# SimpleFPGA_SI_Demo.net
KiCad netlist of a schematic drawn in Altium Designer
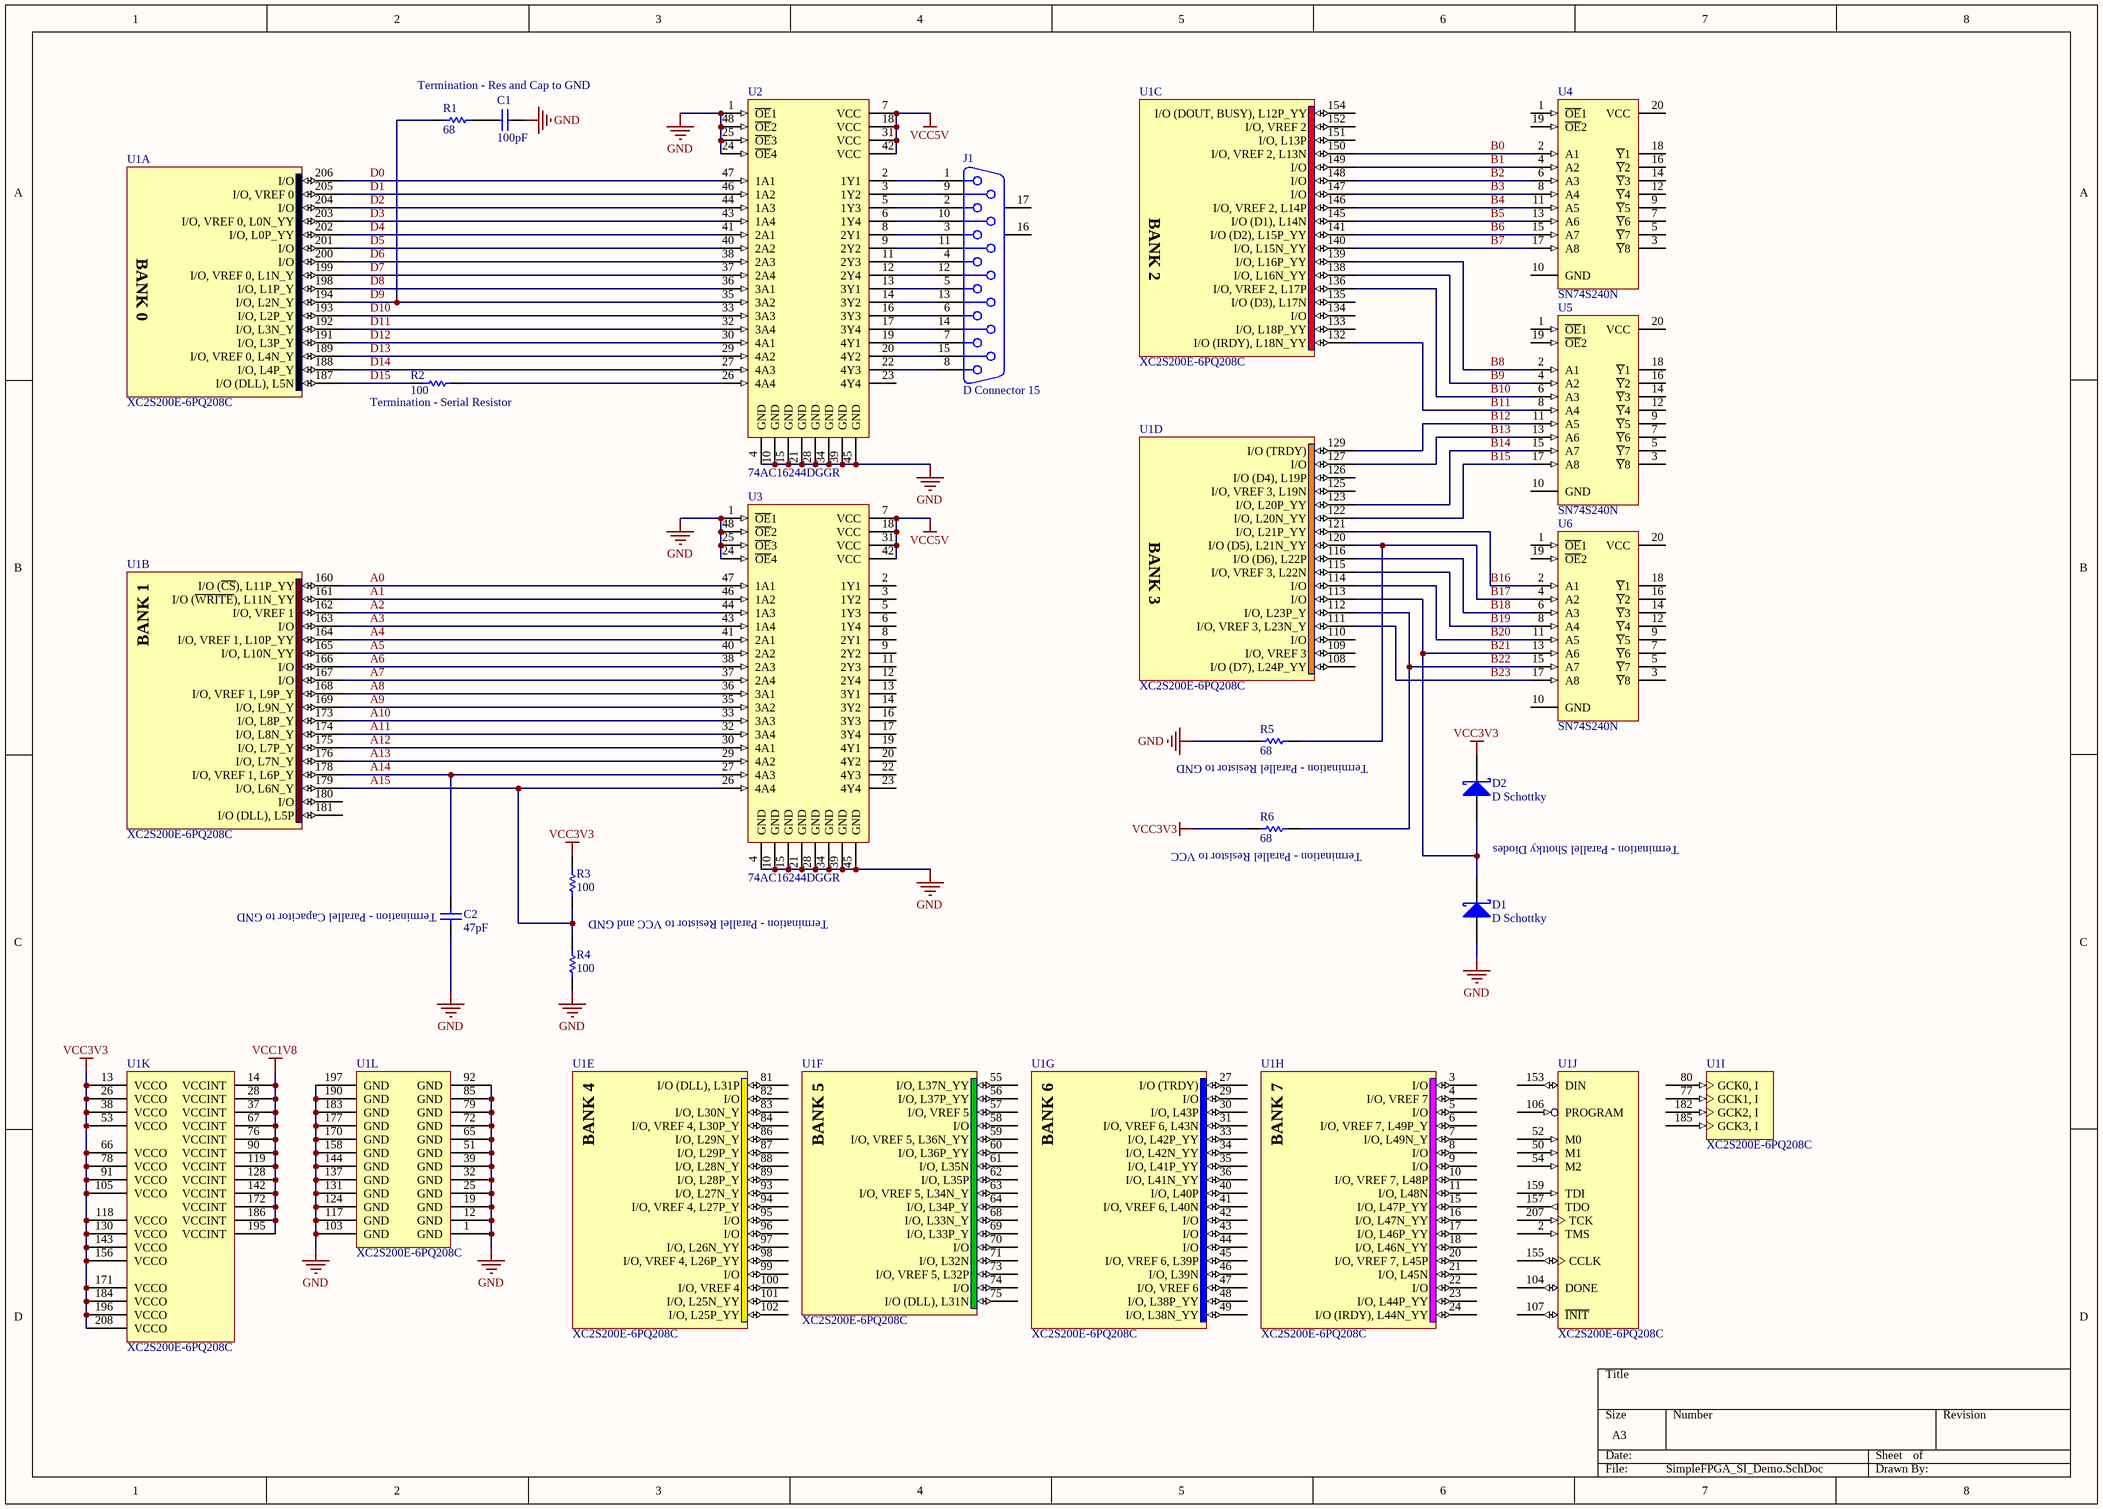
[diagram p0: SimpleFPGA_SI_Demo.SchDoc]

(export (version "E")
  (design (tool "Eeschema 10.0.6"))
  (components
    (comp (ref "C1")
      (value "100pF")
      (footprint "RAD-0.3")
      (description "Capacitor")
      (fields (field (name "Comment") "Cap"))
      (libsource (lib "Miscellaneous Devices") (part "Cap"))
    )
    (comp (ref "C2")
      (value "47pF")
      (footprint "RAD-0.3")
      (description "Capacitor")
      (fields (field (name "Comment") "Cap"))
      (libsource (lib "Miscellaneous Devices") (part "Cap"))
    )
    (comp (ref "D1")
      (value "D Schottky")
      (footprint "SMB")
      (description "Schottky Diode")
      (libsource (lib "Miscellaneous Devices") (part "D Schottky"))
    )
    (comp (ref "D2")
      (value "D Schottky")
      (footprint "SMB")
      (description "Schottky Diode")
      (libsource (lib "Miscellaneous Devices") (part "D Schottky"))
    )
    (comp (ref "J1")
      (value "D Connector 15")
      (footprint "DSUB1.385-2H15")
      (description "Receptacle Assembly, 15 Position, Right Angle")
      (libsource (lib "Miscellaneous Connectors") (part "D Connector 15"))
    )
    (comp (ref "R1")
      (value "68")
      (footprint "AXIAL-0.3")
      (description "Resistor")
      (fields (field (name "Comment") "Res1"))
      (libsource (lib "Miscellaneous Devices") (part "Res1"))
    )
    (comp (ref "R2")
      (value "100")
      (footprint "AXIAL-0.3")
      (description "Resistor")
      (fields (field (name "Comment") "Res1"))
      (libsource (lib "Miscellaneous Devices") (part "Res1"))
    )
    (comp (ref "R3")
      (value "100")
      (footprint "AXIAL-0.3")
      (description "Resistor")
      (fields (field (name "Comment") "Res1"))
      (libsource (lib "Miscellaneous Devices") (part "Res1"))
    )
    (comp (ref "R4")
      (value "100")
      (footprint "AXIAL-0.3")
      (description "Resistor")
      (fields (field (name "Comment") "Res1"))
      (libsource (lib "Miscellaneous Devices") (part "Res1"))
    )
    (comp (ref "R5")
      (value "68")
      (footprint "AXIAL-0.3")
      (description "Resistor")
      (fields (field (name "Comment") "Res1"))
      (libsource (lib "Miscellaneous Devices") (part "Res1"))
    )
    (comp (ref "R6")
      (value "68")
      (footprint "AXIAL-0.3")
      (description "Resistor")
      (fields (field (name "Comment") "Res1"))
      (libsource (lib "Miscellaneous Devices") (part "Res1"))
    )
    (comp (ref "U1")
      (value "XC2S200E-6PQ208C")
      (footprint "PQ208_N")
      (description "Spartan-IIE 1.8V FPGA, 208-Pin PQFP, Standard Performance, Commercial Grade")
      (libsource (lib "Xilinx Spartan-IIE") (part "XC2S200E-6PQ208C"))
    )
    (comp (ref "U2")
      (value "74AC16244DGGR")
      (footprint "DGG048")
      (description "16-Bit Buffer/Line Driver with 3-State Outputs")
      (libsource (lib "TI Logic Buffer Line Driver") (part "74AC16244DGGR"))
    )
    (comp (ref "U3")
      (value "74AC16244DGGR")
      (footprint "DGG048")
      (description "16-Bit Buffer/Line Driver with 3-State Outputs")
      (libsource (lib "TI Logic Buffer Line Driver") (part "74AC16244DGGR"))
    )
    (comp (ref "U4")
      (value "SN74S240N")
      (footprint "N020")
      (description "Octal Buffer and Line Driver with 3-State Outputs")
      (libsource (lib "TI Logic Buffer Line Driver") (part "SN74S240N"))
    )
    (comp (ref "U5")
      (value "SN74S240N")
      (footprint "N020")
      (description "Octal Buffer and Line Driver with 3-State Outputs")
      (libsource (lib "TI Logic Buffer Line Driver") (part "SN74S240N"))
    )
    (comp (ref "U6")
      (value "SN74S240N")
      (footprint "N020")
      (description "Octal Buffer and Line Driver with 3-State Outputs")
      (libsource (lib "TI Logic Buffer Line Driver") (part "SN74S240N"))
    )
  )
  (nets
    (net (code "1") (name "/A0") (class "Default")
      (node (ref "U1") (pin "160") (pinfunction "I/O_(~{CS}),_L11P_YY_160") (pintype "bidirectional"))
      (node (ref "U3") (pin "47") (pinfunction "1A1_47") (pintype "input"))
    )
    (net (code "2") (name "/A1") (class "Default")
      (node (ref "U1") (pin "161") (pinfunction "I/O_(~{WRITE}),_L11N_YY_161") (pintype "bidirectional"))
      (node (ref "U3") (pin "46") (pinfunction "1A2_46") (pintype "input"))
    )
    (net (code "3") (name "/A2") (class "Default")
      (node (ref "U1") (pin "162") (pinfunction "I/O,_VREF_1_162") (pintype "bidirectional"))
      (node (ref "U3") (pin "44") (pinfunction "1A3_44") (pintype "input"))
    )
    (net (code "4") (name "/A3") (class "Default")
      (node (ref "U1") (pin "163") (pinfunction "I/O_163") (pintype "bidirectional"))
      (node (ref "U3") (pin "43") (pinfunction "1A4_43") (pintype "input"))
    )
    (net (code "5") (name "/A4") (class "Default")
      (node (ref "U1") (pin "164") (pinfunction "I/O,_VREF_1,_L10P_YY_164") (pintype "bidirectional"))
      (node (ref "U3") (pin "41") (pinfunction "2A1_41") (pintype "input"))
    )
    (net (code "6") (name "/A5") (class "Default")
      (node (ref "U1") (pin "165") (pinfunction "I/O,_L10N_YY_165") (pintype "bidirectional"))
      (node (ref "U3") (pin "40") (pinfunction "2A2_40") (pintype "input"))
    )
    (net (code "7") (name "/A6") (class "Default")
      (node (ref "U1") (pin "166") (pinfunction "I/O_166") (pintype "bidirectional"))
      (node (ref "U3") (pin "38") (pinfunction "2A3_38") (pintype "input"))
    )
    (net (code "8") (name "/A7") (class "Default")
      (node (ref "U1") (pin "167") (pinfunction "I/O_167") (pintype "bidirectional"))
      (node (ref "U3") (pin "37") (pinfunction "2A4_37") (pintype "input"))
    )
    (net (code "9") (name "/A8") (class "Default")
      (node (ref "U1") (pin "168") (pinfunction "I/O,_VREF_1,_L9P_Y_168") (pintype "bidirectional"))
      (node (ref "U3") (pin "36") (pinfunction "3A1_36") (pintype "input"))
    )
    (net (code "10") (name "/A9") (class "Default")
      (node (ref "U1") (pin "169") (pinfunction "I/O,_L9N_Y_169") (pintype "bidirectional"))
      (node (ref "U3") (pin "35") (pinfunction "3A2_35") (pintype "input"))
    )
    (net (code "11") (name "/A10") (class "Default")
      (node (ref "U1") (pin "173") (pinfunction "I/O,_L8P_Y_173") (pintype "bidirectional"))
      (node (ref "U3") (pin "33") (pinfunction "3A3_33") (pintype "input"))
    )
    (net (code "12") (name "/A11") (class "Default")
      (node (ref "U1") (pin "174") (pinfunction "I/O,_L8N_Y_174") (pintype "bidirectional"))
      (node (ref "U3") (pin "32") (pinfunction "3A4_32") (pintype "input"))
    )
    (net (code "13") (name "/A12") (class "Default")
      (node (ref "U1") (pin "175") (pinfunction "I/O,_L7P_Y_175") (pintype "bidirectional"))
      (node (ref "U3") (pin "30") (pinfunction "4A1_30") (pintype "input"))
    )
    (net (code "14") (name "/A13") (class "Default")
      (node (ref "U1") (pin "176") (pinfunction "I/O,_L7N_Y_176") (pintype "bidirectional"))
      (node (ref "U3") (pin "29") (pinfunction "4A2_29") (pintype "input"))
    )
    (net (code "15") (name "/A14") (class "Default")
      (node (ref "C2") (pin "2") (pinfunction "2_2") (pintype "passive"))
      (node (ref "U1") (pin "178") (pinfunction "I/O,_VREF_1,_L6P_Y_178") (pintype "bidirectional"))
      (node (ref "U3") (pin "27") (pinfunction "4A3_27") (pintype "input"))
    )
    (net (code "16") (name "/A15") (class "Default")
      (node (ref "R3") (pin "1") (pinfunction "1_1") (pintype "passive"))
      (node (ref "R4") (pin "2") (pinfunction "2_2") (pintype "passive"))
      (node (ref "U1") (pin "179") (pinfunction "I/O,_L6N_Y_179") (pintype "bidirectional"))
      (node (ref "U3") (pin "26") (pinfunction "4A4_26") (pintype "input"))
    )
    (net (code "17") (name "/B0") (class "Default")
      (node (ref "U1") (pin "150") (pinfunction "I/O,_VREF_2,_L13N_150") (pintype "bidirectional"))
      (node (ref "U4") (pin "2") (pinfunction "A1_2") (pintype "input"))
    )
    (net (code "18") (name "/B1") (class "Default")
      (node (ref "U1") (pin "149") (pinfunction "I/O_149") (pintype "bidirectional"))
      (node (ref "U4") (pin "4") (pinfunction "A2_4") (pintype "input"))
    )
    (net (code "19") (name "/B2") (class "Default")
      (node (ref "U1") (pin "148") (pinfunction "I/O_148") (pintype "bidirectional"))
      (node (ref "U4") (pin "6") (pinfunction "A3_6") (pintype "input"))
    )
    (net (code "20") (name "/B3") (class "Default")
      (node (ref "U1") (pin "147") (pinfunction "I/O_147") (pintype "bidirectional"))
      (node (ref "U4") (pin "8") (pinfunction "A4_8") (pintype "input"))
    )
    (net (code "21") (name "/B4") (class "Default")
      (node (ref "U1") (pin "146") (pinfunction "I/O,_VREF_2,_L14P_146") (pintype "bidirectional"))
      (node (ref "U4") (pin "11") (pinfunction "A5_11") (pintype "input"))
    )
    (net (code "22") (name "/B5") (class "Default")
      (node (ref "U1") (pin "145") (pinfunction "I/O_(D1),_L14N_145") (pintype "bidirectional"))
      (node (ref "U4") (pin "13") (pinfunction "A6_13") (pintype "input"))
    )
    (net (code "23") (name "/B6") (class "Default")
      (node (ref "U1") (pin "141") (pinfunction "I/O_(D2),_L15P_YY_141") (pintype "bidirectional"))
      (node (ref "U4") (pin "15") (pinfunction "A7_15") (pintype "input"))
    )
    (net (code "24") (name "/B7") (class "Default")
      (node (ref "U1") (pin "140") (pinfunction "I/O,_L15N_YY_140") (pintype "bidirectional"))
      (node (ref "U4") (pin "17") (pinfunction "A8_17") (pintype "input"))
    )
    (net (code "25") (name "/B8") (class "Default")
      (node (ref "U1") (pin "139") (pinfunction "I/O,_L16P_YY_139") (pintype "bidirectional"))
      (node (ref "U5") (pin "2") (pinfunction "A1_2") (pintype "input"))
    )
    (net (code "26") (name "/B9") (class "Default")
      (node (ref "U1") (pin "138") (pinfunction "I/O,_L16N_YY_138") (pintype "bidirectional"))
      (node (ref "U5") (pin "4") (pinfunction "A2_4") (pintype "input"))
    )
    (net (code "27") (name "/B10") (class "Default")
      (node (ref "U1") (pin "136") (pinfunction "I/O,_VREF_2,_L17P_136") (pintype "bidirectional"))
      (node (ref "U5") (pin "6") (pinfunction "A3_6") (pintype "input"))
    )
    (net (code "28") (name "/B11") (class "Default")
      (node (ref "U1") (pin "132") (pinfunction "I/O_(IRDY),_L18N_YY_132") (pintype "bidirectional"))
      (node (ref "U5") (pin "8") (pinfunction "A4_8") (pintype "input"))
    )
    (net (code "29") (name "/B12") (class "Default")
      (node (ref "U1") (pin "129") (pinfunction "I/O_(TRDY)_129") (pintype "bidirectional"))
      (node (ref "U5") (pin "11") (pinfunction "A5_11") (pintype "input"))
    )
    (net (code "30") (name "/B13") (class "Default")
      (node (ref "U1") (pin "127") (pinfunction "I/O_127") (pintype "bidirectional"))
      (node (ref "U5") (pin "13") (pinfunction "A6_13") (pintype "input"))
    )
    (net (code "31") (name "/B14") (class "Default")
      (node (ref "U1") (pin "123") (pinfunction "I/O,_L20P_YY_123") (pintype "bidirectional"))
      (node (ref "U5") (pin "15") (pinfunction "A7_15") (pintype "input"))
    )
    (net (code "32") (name "/B15") (class "Default")
      (node (ref "U1") (pin "122") (pinfunction "I/O,_L20N_YY_122") (pintype "bidirectional"))
      (node (ref "U5") (pin "17") (pinfunction "A8_17") (pintype "input"))
    )
    (net (code "33") (name "/B16") (class "Default")
      (node (ref "U1") (pin "121") (pinfunction "I/O,_L21P_YY_121") (pintype "bidirectional"))
      (node (ref "U6") (pin "2") (pinfunction "A1_2") (pintype "input"))
    )
    (net (code "34") (name "/B17") (class "Default")
      (node (ref "R5") (pin "2") (pinfunction "2_2") (pintype "passive"))
      (node (ref "U1") (pin "120") (pinfunction "I/O_(D5),_L21N_YY_120") (pintype "bidirectional"))
      (node (ref "U6") (pin "4") (pinfunction "A2_4") (pintype "input"))
    )
    (net (code "35") (name "/B18") (class "Default")
      (node (ref "U1") (pin "116") (pinfunction "I/O_(D6),_L22P_116") (pintype "bidirectional"))
      (node (ref "U6") (pin "6") (pinfunction "A3_6") (pintype "input"))
    )
    (net (code "36") (name "/B19") (class "Default")
      (node (ref "U1") (pin "115") (pinfunction "I/O,_VREF_3,_L22N_115") (pintype "bidirectional"))
      (node (ref "U6") (pin "8") (pinfunction "A4_8") (pintype "input"))
    )
    (net (code "37") (name "/B20") (class "Default")
      (node (ref "U1") (pin "114") (pinfunction "I/O_114") (pintype "bidirectional"))
      (node (ref "U6") (pin "11") (pinfunction "A5_11") (pintype "input"))
    )
    (net (code "38") (name "/B21") (class "Default")
      (node (ref "D1") (pin "2") (pinfunction "K_2") (pintype "passive"))
      (node (ref "D2") (pin "1") (pinfunction "A_1") (pintype "passive"))
      (node (ref "U1") (pin "113") (pinfunction "I/O_113") (pintype "bidirectional"))
      (node (ref "U6") (pin "13") (pinfunction "A6_13") (pintype "input"))
    )
    (net (code "39") (name "/B22") (class "Default")
      (node (ref "R6") (pin "2") (pinfunction "2_2") (pintype "passive"))
      (node (ref "U1") (pin "112") (pinfunction "I/O,_L23P_Y_112") (pintype "bidirectional"))
      (node (ref "U6") (pin "15") (pinfunction "A7_15") (pintype "input"))
    )
    (net (code "40") (name "/B23") (class "Default")
      (node (ref "U1") (pin "111") (pinfunction "I/O,_VREF_3,_L23N_Y_111") (pintype "bidirectional"))
      (node (ref "U6") (pin "17") (pinfunction "A8_17") (pintype "input"))
    )
    (net (code "41") (name "/D0") (class "Default")
      (node (ref "U1") (pin "206") (pinfunction "I/O_206") (pintype "bidirectional"))
      (node (ref "U2") (pin "47") (pinfunction "1A1_47") (pintype "input"))
    )
    (net (code "42") (name "/D1") (class "Default")
      (node (ref "U1") (pin "205") (pinfunction "I/O,_VREF_0_205") (pintype "bidirectional"))
      (node (ref "U2") (pin "46") (pinfunction "1A2_46") (pintype "input"))
    )
    (net (code "43") (name "/D2") (class "Default")
      (node (ref "U1") (pin "204") (pinfunction "I/O_204") (pintype "bidirectional"))
      (node (ref "U2") (pin "44") (pinfunction "1A3_44") (pintype "input"))
    )
    (net (code "44") (name "/D3") (class "Default")
      (node (ref "U1") (pin "203") (pinfunction "I/O,_VREF_0,_L0N_YY_203") (pintype "bidirectional"))
      (node (ref "U2") (pin "43") (pinfunction "1A4_43") (pintype "input"))
    )
    (net (code "45") (name "/D4") (class "Default")
      (node (ref "U1") (pin "202") (pinfunction "I/O,_L0P_YY_202") (pintype "bidirectional"))
      (node (ref "U2") (pin "41") (pinfunction "2A1_41") (pintype "input"))
    )
    (net (code "46") (name "/D5") (class "Default")
      (node (ref "U1") (pin "201") (pinfunction "I/O_201") (pintype "bidirectional"))
      (node (ref "U2") (pin "40") (pinfunction "2A2_40") (pintype "input"))
    )
    (net (code "47") (name "/D6") (class "Default")
      (node (ref "U1") (pin "200") (pinfunction "I/O_200") (pintype "bidirectional"))
      (node (ref "U2") (pin "38") (pinfunction "2A3_38") (pintype "input"))
    )
    (net (code "48") (name "/D7") (class "Default")
      (node (ref "U1") (pin "199") (pinfunction "I/O,_VREF_0,_L1N_Y_199") (pintype "bidirectional"))
      (node (ref "U2") (pin "37") (pinfunction "2A4_37") (pintype "input"))
    )
    (net (code "49") (name "/D8") (class "Default")
      (node (ref "U1") (pin "198") (pinfunction "I/O,_L1P_Y_198") (pintype "bidirectional"))
      (node (ref "U2") (pin "36") (pinfunction "3A1_36") (pintype "input"))
    )
    (net (code "50") (name "/D9") (class "Default")
      (node (ref "R1") (pin "1") (pinfunction "1_1") (pintype "passive"))
      (node (ref "U1") (pin "194") (pinfunction "I/O,_L2N_Y_194") (pintype "bidirectional"))
      (node (ref "U2") (pin "35") (pinfunction "3A2_35") (pintype "input"))
    )
    (net (code "51") (name "/D10") (class "Default")
      (node (ref "U1") (pin "193") (pinfunction "I/O,_L2P_Y_193") (pintype "bidirectional"))
      (node (ref "U2") (pin "33") (pinfunction "3A3_33") (pintype "input"))
    )
    (net (code "52") (name "/D11") (class "Default")
      (node (ref "U1") (pin "192") (pinfunction "I/O,_L3N_Y_192") (pintype "bidirectional"))
      (node (ref "U2") (pin "32") (pinfunction "3A4_32") (pintype "input"))
    )
    (net (code "53") (name "/D12") (class "Default")
      (node (ref "U1") (pin "191") (pinfunction "I/O,_L3P_Y_191") (pintype "bidirectional"))
      (node (ref "U2") (pin "30") (pinfunction "4A1_30") (pintype "input"))
    )
    (net (code "54") (name "/D13") (class "Default")
      (node (ref "U1") (pin "189") (pinfunction "I/O,_VREF_0,_L4N_Y_189") (pintype "bidirectional"))
      (node (ref "U2") (pin "29") (pinfunction "4A2_29") (pintype "input"))
    )
    (net (code "55") (name "/D14") (class "Default")
      (node (ref "U1") (pin "188") (pinfunction "I/O,_L4P_Y_188") (pintype "bidirectional"))
      (node (ref "U2") (pin "27") (pinfunction "4A3_27") (pintype "input"))
    )
    (net (code "56") (name "/D15") (class "Default")
      (node (ref "R2") (pin "1") (pinfunction "1_1") (pintype "passive"))
      (node (ref "U1") (pin "187") (pinfunction "I/O_(DLL),_L5N_187") (pintype "bidirectional"))
    )
    (net (code "57") (name "GND") (class "Default")
      (node (ref "C1") (pin "2") (pinfunction "2_2") (pintype "passive"))
      (node (ref "C2") (pin "1") (pinfunction "1_1") (pintype "passive"))
      (node (ref "D1") (pin "1") (pinfunction "A_1") (pintype "passive"))
      (node (ref "R4") (pin "1") (pinfunction "1_1") (pintype "passive"))
      (node (ref "R5") (pin "1") (pinfunction "1_1") (pintype "passive"))
      (node (ref "U1") (pin "1") (pinfunction "GND_1") (pintype "power_in"))
      (node (ref "U1") (pin "103") (pinfunction "GND_103") (pintype "power_in"))
      (node (ref "U1") (pin "117") (pinfunction "GND_117") (pintype "power_in"))
      (node (ref "U1") (pin "12") (pinfunction "GND_12") (pintype "power_in"))
      (node (ref "U1") (pin "124") (pinfunction "GND_124") (pintype "power_in"))
      (node (ref "U1") (pin "131") (pinfunction "GND_131") (pintype "power_in"))
      (node (ref "U1") (pin "137") (pinfunction "GND_137") (pintype "power_in"))
      (node (ref "U1") (pin "144") (pinfunction "GND_144") (pintype "power_in"))
      (node (ref "U1") (pin "158") (pinfunction "GND_158") (pintype "power_in"))
      (node (ref "U1") (pin "170") (pinfunction "GND_170") (pintype "power_in"))
      (node (ref "U1") (pin "177") (pinfunction "GND_177") (pintype "power_in"))
      (node (ref "U1") (pin "183") (pinfunction "GND_183") (pintype "power_in"))
      (node (ref "U1") (pin "19") (pinfunction "GND_19") (pintype "power_in"))
      (node (ref "U1") (pin "190") (pinfunction "GND_190") (pintype "power_in"))
      (node (ref "U1") (pin "197") (pinfunction "GND_197") (pintype "power_in"))
      (node (ref "U1") (pin "25") (pinfunction "GND_25") (pintype "power_in"))
      (node (ref "U1") (pin "32") (pinfunction "GND_32") (pintype "power_in"))
      (node (ref "U1") (pin "39") (pinfunction "GND_39") (pintype "power_in"))
      (node (ref "U1") (pin "51") (pinfunction "GND_51") (pintype "power_in"))
      (node (ref "U1") (pin "65") (pinfunction "GND_65") (pintype "power_in"))
      (node (ref "U1") (pin "72") (pinfunction "GND_72") (pintype "power_in"))
      (node (ref "U1") (pin "79") (pinfunction "GND_79") (pintype "power_in"))
      (node (ref "U1") (pin "85") (pinfunction "GND_85") (pintype "power_in"))
      (node (ref "U1") (pin "92") (pinfunction "GND_92") (pintype "power_in"))
      (node (ref "U2") (pin "1") (pinfunction "~{OE}1_1") (pintype "input"))
      (node (ref "U2") (pin "10") (pinfunction "GND_10") (pintype "power_in"))
      (node (ref "U2") (pin "15") (pinfunction "GND_15") (pintype "power_in"))
      (node (ref "U2") (pin "21") (pinfunction "GND_21") (pintype "power_in"))
      (node (ref "U2") (pin "24") (pinfunction "~{OE}4_24") (pintype "input"))
      (node (ref "U2") (pin "25") (pinfunction "~{OE}3_25") (pintype "input"))
      (node (ref "U2") (pin "28") (pinfunction "GND_28") (pintype "power_in"))
      (node (ref "U2") (pin "34") (pinfunction "GND_34") (pintype "power_in"))
      (node (ref "U2") (pin "39") (pinfunction "GND_39") (pintype "power_in"))
      (node (ref "U2") (pin "4") (pinfunction "GND_4") (pintype "power_in"))
      (node (ref "U2") (pin "45") (pinfunction "GND_45") (pintype "power_in"))
      (node (ref "U2") (pin "48") (pinfunction "~{OE}2_48") (pintype "input"))
      (node (ref "U3") (pin "1") (pinfunction "~{OE}1_1") (pintype "input"))
      (node (ref "U3") (pin "10") (pinfunction "GND_10") (pintype "power_in"))
      (node (ref "U3") (pin "15") (pinfunction "GND_15") (pintype "power_in"))
      (node (ref "U3") (pin "21") (pinfunction "GND_21") (pintype "power_in"))
      (node (ref "U3") (pin "24") (pinfunction "~{OE}4_24") (pintype "input"))
      (node (ref "U3") (pin "25") (pinfunction "~{OE}3_25") (pintype "input"))
      (node (ref "U3") (pin "28") (pinfunction "GND_28") (pintype "power_in"))
      (node (ref "U3") (pin "34") (pinfunction "GND_34") (pintype "power_in"))
      (node (ref "U3") (pin "39") (pinfunction "GND_39") (pintype "power_in"))
      (node (ref "U3") (pin "4") (pinfunction "GND_4") (pintype "power_in"))
      (node (ref "U3") (pin "45") (pinfunction "GND_45") (pintype "power_in"))
      (node (ref "U3") (pin "48") (pinfunction "~{OE}2_48") (pintype "input"))
    )
    (net (code "58") (name "Net-(C1-Pad1)") (class "Default")
      (node (ref "C1") (pin "1") (pinfunction "1_1") (pintype "passive"))
      (node (ref "R1") (pin "2") (pinfunction "2_2") (pintype "passive"))
    )
    (net (code "59") (name "Net-(U2-1Y1)") (class "Default")
      (node (ref "J1") (pin "1") (pinfunction "1_1") (pintype "passive"))
      (node (ref "U2") (pin "2") (pinfunction "1Y1_2") (pintype "tri_state"))
    )
    (net (code "60") (name "Net-(U2-1Y2)") (class "Default")
      (node (ref "J1") (pin "9") (pinfunction "9_9") (pintype "passive"))
      (node (ref "U2") (pin "3") (pinfunction "1Y2_3") (pintype "tri_state"))
    )
    (net (code "61") (name "Net-(U2-1Y3)") (class "Default")
      (node (ref "J1") (pin "2") (pinfunction "2_2") (pintype "passive"))
      (node (ref "U2") (pin "5") (pinfunction "1Y3_5") (pintype "tri_state"))
    )
    (net (code "62") (name "Net-(U2-1Y4)") (class "Default")
      (node (ref "J1") (pin "10") (pinfunction "10_10") (pintype "passive"))
      (node (ref "U2") (pin "6") (pinfunction "1Y4_6") (pintype "tri_state"))
    )
    (net (code "63") (name "Net-(U2-2Y1)") (class "Default")
      (node (ref "J1") (pin "3") (pinfunction "3_3") (pintype "passive"))
      (node (ref "U2") (pin "8") (pinfunction "2Y1_8") (pintype "tri_state"))
    )
    (net (code "64") (name "Net-(U2-2Y2)") (class "Default")
      (node (ref "J1") (pin "11") (pinfunction "11_11") (pintype "passive"))
      (node (ref "U2") (pin "9") (pinfunction "2Y2_9") (pintype "tri_state"))
    )
    (net (code "65") (name "Net-(U2-2Y3)") (class "Default")
      (node (ref "J1") (pin "4") (pinfunction "4_4") (pintype "passive"))
      (node (ref "U2") (pin "11") (pinfunction "2Y3_11") (pintype "tri_state"))
    )
    (net (code "66") (name "Net-(U2-2Y4)") (class "Default")
      (node (ref "J1") (pin "12") (pinfunction "12_12") (pintype "passive"))
      (node (ref "U2") (pin "12") (pinfunction "2Y4_12") (pintype "tri_state"))
    )
    (net (code "67") (name "Net-(U2-3Y1)") (class "Default")
      (node (ref "J1") (pin "5") (pinfunction "5_5") (pintype "passive"))
      (node (ref "U2") (pin "13") (pinfunction "3Y1_13") (pintype "tri_state"))
    )
    (net (code "68") (name "Net-(U2-3Y2)") (class "Default")
      (node (ref "J1") (pin "13") (pinfunction "13_13") (pintype "passive"))
      (node (ref "U2") (pin "14") (pinfunction "3Y2_14") (pintype "tri_state"))
    )
    (net (code "69") (name "Net-(U2-3Y3)") (class "Default")
      (node (ref "J1") (pin "6") (pinfunction "6_6") (pintype "passive"))
      (node (ref "U2") (pin "16") (pinfunction "3Y3_16") (pintype "tri_state"))
    )
    (net (code "70") (name "Net-(U2-3Y4)") (class "Default")
      (node (ref "J1") (pin "14") (pinfunction "14_14") (pintype "passive"))
      (node (ref "U2") (pin "17") (pinfunction "3Y4_17") (pintype "tri_state"))
    )
    (net (code "71") (name "Net-(U2-4A4)") (class "Default")
      (node (ref "R2") (pin "2") (pinfunction "2_2") (pintype "passive"))
      (node (ref "U2") (pin "26") (pinfunction "4A4_26") (pintype "input"))
    )
    (net (code "72") (name "Net-(U2-4Y1)") (class "Default")
      (node (ref "J1") (pin "7") (pinfunction "7_7") (pintype "passive"))
      (node (ref "U2") (pin "19") (pinfunction "4Y1_19") (pintype "tri_state"))
    )
    (net (code "73") (name "Net-(U2-4Y2)") (class "Default")
      (node (ref "J1") (pin "15") (pinfunction "15_15") (pintype "passive"))
      (node (ref "U2") (pin "20") (pinfunction "4Y2_20") (pintype "tri_state"))
    )
    (net (code "74") (name "Net-(U2-4Y3)") (class "Default")
      (node (ref "J1") (pin "8") (pinfunction "8_8") (pintype "passive"))
      (node (ref "U2") (pin "22") (pinfunction "4Y3_22") (pintype "tri_state"))
    )
    (net (code "75") (name "VCC1V8") (class "Default")
      (node (ref "U1") (pin "119") (pinfunction "VCCINT_119") (pintype "power_in"))
      (node (ref "U1") (pin "128") (pinfunction "VCCINT_128") (pintype "power_in"))
      (node (ref "U1") (pin "14") (pinfunction "VCCINT_14") (pintype "power_in"))
      (node (ref "U1") (pin "142") (pinfunction "VCCINT_142") (pintype "power_in"))
      (node (ref "U1") (pin "172") (pinfunction "VCCINT_172") (pintype "power_in"))
      (node (ref "U1") (pin "186") (pinfunction "VCCINT_186") (pintype "power_in"))
      (node (ref "U1") (pin "195") (pinfunction "VCCINT_195") (pintype "power_in"))
      (node (ref "U1") (pin "28") (pinfunction "VCCINT_28") (pintype "power_in"))
      (node (ref "U1") (pin "37") (pinfunction "VCCINT_37") (pintype "power_in"))
      (node (ref "U1") (pin "67") (pinfunction "VCCINT_67") (pintype "power_in"))
      (node (ref "U1") (pin "76") (pinfunction "VCCINT_76") (pintype "power_in"))
      (node (ref "U1") (pin "90") (pinfunction "VCCINT_90") (pintype "power_in"))
    )
    (net (code "76") (name "VCC3V3") (class "Default")
      (node (ref "D2") (pin "2") (pinfunction "K_2") (pintype "passive"))
      (node (ref "R3") (pin "2") (pinfunction "2_2") (pintype "passive"))
      (node (ref "R6") (pin "1") (pinfunction "1_1") (pintype "passive"))
      (node (ref "U1") (pin "105") (pinfunction "VCCO_105") (pintype "power_in"))
      (node (ref "U1") (pin "118") (pinfunction "VCCO_118") (pintype "power_in"))
      (node (ref "U1") (pin "13") (pinfunction "VCCO_13") (pintype "power_in"))
      (node (ref "U1") (pin "130") (pinfunction "VCCO_130") (pintype "power_in"))
      (node (ref "U1") (pin "143") (pinfunction "VCCO_143") (pintype "power_in"))
      (node (ref "U1") (pin "156") (pinfunction "VCCO_156") (pintype "power_in"))
      (node (ref "U1") (pin "171") (pinfunction "VCCO_171") (pintype "power_in"))
      (node (ref "U1") (pin "184") (pinfunction "VCCO_184") (pintype "power_in"))
      (node (ref "U1") (pin "196") (pinfunction "VCCO_196") (pintype "power_in"))
      (node (ref "U1") (pin "208") (pinfunction "VCCO_208") (pintype "power_in"))
      (node (ref "U1") (pin "26") (pinfunction "VCCO_26") (pintype "power_in"))
      (node (ref "U1") (pin "38") (pinfunction "VCCO_38") (pintype "power_in"))
      (node (ref "U1") (pin "53") (pinfunction "VCCO_53") (pintype "power_in"))
      (node (ref "U1") (pin "66") (pinfunction "VCCO_66") (pintype "power_in"))
      (node (ref "U1") (pin "78") (pinfunction "VCCO_78") (pintype "power_in"))
      (node (ref "U1") (pin "91") (pinfunction "VCCO_91") (pintype "power_in"))
    )
    (net (code "77") (name "VCC5V") (class "Default")
      (node (ref "U2") (pin "18") (pinfunction "VCC_18") (pintype "power_in"))
      (node (ref "U2") (pin "31") (pinfunction "VCC_31") (pintype "power_in"))
      (node (ref "U2") (pin "42") (pinfunction "VCC_42") (pintype "power_in"))
      (node (ref "U2") (pin "7") (pinfunction "VCC_7") (pintype "power_in"))
      (node (ref "U3") (pin "18") (pinfunction "VCC_18") (pintype "power_in"))
      (node (ref "U3") (pin "31") (pinfunction "VCC_31") (pintype "power_in"))
      (node (ref "U3") (pin "42") (pinfunction "VCC_42") (pintype "power_in"))
      (node (ref "U3") (pin "7") (pinfunction "VCC_7") (pintype "power_in"))
    )
    (net (code "78") (name "unconnected-(J1-MH1-Pad16)") (class "Default")
      (node (ref "J1") (pin "16") (pinfunction "MH1_16") (pintype "passive"))
    )
    (net (code "79") (name "unconnected-(J1-MH2-Pad17)") (class "Default")
      (node (ref "J1") (pin "17") (pinfunction "MH2_17") (pintype "passive"))
    )
    (net (code "80") (name "unconnected-(U1B-I{slash}O-Pad180)") (class "Default")
      (node (ref "U1") (pin "180") (pinfunction "I/O_180") (pintype "bidirectional"))
    )
    (net (code "81") (name "unconnected-(U1B-I{slash}O_(DLL),_L5P-Pad181)") (class "Default")
      (node (ref "U1") (pin "181") (pinfunction "I/O_(DLL),_L5P_181") (pintype "bidirectional"))
    )
    (net (code "82") (name "unconnected-(U1C-I{slash}O,_L13P-Pad151)") (class "Default")
      (node (ref "U1") (pin "151") (pinfunction "I/O,_L13P_151") (pintype "bidirectional"))
    )
    (net (code "83") (name "unconnected-(U1C-I{slash}O,_L18P_YY-Pad133)") (class "Default")
      (node (ref "U1") (pin "133") (pinfunction "I/O,_L18P_YY_133") (pintype "bidirectional"))
    )
    (net (code "84") (name "unconnected-(U1C-I{slash}O,_VREF_2-Pad152)") (class "Default")
      (node (ref "U1") (pin "152") (pinfunction "I/O,_VREF_2_152") (pintype "bidirectional"))
    )
    (net (code "85") (name "unconnected-(U1C-I{slash}O-Pad134)") (class "Default")
      (node (ref "U1") (pin "134") (pinfunction "I/O_134") (pintype "bidirectional"))
    )
    (net (code "86") (name "unconnected-(U1C-I{slash}O_(D3),_L17N-Pad135)") (class "Default")
      (node (ref "U1") (pin "135") (pinfunction "I/O_(D3),_L17N_135") (pintype "bidirectional"))
    )
    (net (code "87") (name "unconnected-(U1C-I{slash}O_(DOUT,_BUSY),_L12P_YY-Pad154)") (class "Default")
      (node (ref "U1") (pin "154") (pinfunction "I/O_(DOUT,_BUSY),_L12P_YY_154") (pintype "bidirectional"))
    )
    (net (code "88") (name "unconnected-(U1D-I{slash}O,_VREF_3,_L19N-Pad125)") (class "Default")
      (node (ref "U1") (pin "125") (pinfunction "I/O,_VREF_3,_L19N_125") (pintype "bidirectional"))
    )
    (net (code "89") (name "unconnected-(U1D-I{slash}O,_VREF_3-Pad109)") (class "Default")
      (node (ref "U1") (pin "109") (pinfunction "I/O,_VREF_3_109") (pintype "bidirectional"))
    )
    (net (code "90") (name "unconnected-(U1D-I{slash}O-Pad110)") (class "Default")
      (node (ref "U1") (pin "110") (pinfunction "I/O_110") (pintype "bidirectional"))
    )
    (net (code "91") (name "unconnected-(U1D-I{slash}O_(D4),_L19P-Pad126)") (class "Default")
      (node (ref "U1") (pin "126") (pinfunction "I/O_(D4),_L19P_126") (pintype "bidirectional"))
    )
    (net (code "92") (name "unconnected-(U1D-I{slash}O_(D7),_L24P_YY-Pad108)") (class "Default")
      (node (ref "U1") (pin "108") (pinfunction "I/O_(D7),_L24P_YY_108") (pintype "bidirectional"))
    )
    (net (code "93") (name "unconnected-(U1E-I{slash}O,_L25N_YY-Pad101)") (class "Default")
      (node (ref "U1") (pin "101") (pinfunction "I/O,_L25N_YY_101") (pintype "bidirectional"))
    )
    (net (code "94") (name "unconnected-(U1E-I{slash}O,_L25P_YY-Pad102)") (class "Default")
      (node (ref "U1") (pin "102") (pinfunction "I/O,_L25P_YY_102") (pintype "bidirectional"))
    )
    (net (code "95") (name "unconnected-(U1E-I{slash}O,_L26N_YY-Pad97)") (class "Default")
      (node (ref "U1") (pin "97") (pinfunction "I/O,_L26N_YY_97") (pintype "bidirectional"))
    )
    (net (code "96") (name "unconnected-(U1E-I{slash}O,_L27N_Y-Pad93)") (class "Default")
      (node (ref "U1") (pin "93") (pinfunction "I/O,_L27N_Y_93") (pintype "bidirectional"))
    )
    (net (code "97") (name "unconnected-(U1E-I{slash}O,_L28N_Y-Pad88)") (class "Default")
      (node (ref "U1") (pin "88") (pinfunction "I/O,_L28N_Y_88") (pintype "bidirectional"))
    )
    (net (code "98") (name "unconnected-(U1E-I{slash}O,_L28P_Y-Pad89)") (class "Default")
      (node (ref "U1") (pin "89") (pinfunction "I/O,_L28P_Y_89") (pintype "bidirectional"))
    )
    (net (code "99") (name "unconnected-(U1E-I{slash}O,_L29N_Y-Pad86)") (class "Default")
      (node (ref "U1") (pin "86") (pinfunction "I/O,_L29N_Y_86") (pintype "bidirectional"))
    )
    (net (code "100") (name "unconnected-(U1E-I{slash}O,_L29P_Y-Pad87)") (class "Default")
      (node (ref "U1") (pin "87") (pinfunction "I/O,_L29P_Y_87") (pintype "bidirectional"))
    )
    (net (code "101") (name "unconnected-(U1E-I{slash}O,_L30N_Y-Pad83)") (class "Default")
      (node (ref "U1") (pin "83") (pinfunction "I/O,_L30N_Y_83") (pintype "bidirectional"))
    )
    (net (code "102") (name "unconnected-(U1E-I{slash}O,_VREF_4,_L26P_YY-Pad98)") (class "Default")
      (node (ref "U1") (pin "98") (pinfunction "I/O,_VREF_4,_L26P_YY_98") (pintype "bidirectional"))
    )
    (net (code "103") (name "unconnected-(U1E-I{slash}O,_VREF_4,_L27P_Y-Pad94)") (class "Default")
      (node (ref "U1") (pin "94") (pinfunction "I/O,_VREF_4,_L27P_Y_94") (pintype "bidirectional"))
    )
    (net (code "104") (name "unconnected-(U1E-I{slash}O,_VREF_4,_L30P_Y-Pad84)") (class "Default")
      (node (ref "U1") (pin "84") (pinfunction "I/O,_VREF_4,_L30P_Y_84") (pintype "bidirectional"))
    )
    (net (code "105") (name "unconnected-(U1E-I{slash}O,_VREF_4-Pad100)") (class "Default")
      (node (ref "U1") (pin "100") (pinfunction "I/O,_VREF_4_100") (pintype "bidirectional"))
    )
    (net (code "106") (name "unconnected-(U1E-I{slash}O-Pad82)") (class "Default")
      (node (ref "U1") (pin "82") (pinfunction "I/O_82") (pintype "bidirectional"))
    )
    (net (code "107") (name "unconnected-(U1E-I{slash}O-Pad95)") (class "Default")
      (node (ref "U1") (pin "95") (pinfunction "I/O_95") (pintype "bidirectional"))
    )
    (net (code "108") (name "unconnected-(U1E-I{slash}O-Pad96)") (class "Default")
      (node (ref "U1") (pin "96") (pinfunction "I/O_96") (pintype "bidirectional"))
    )
    (net (code "109") (name "unconnected-(U1E-I{slash}O-Pad99)") (class "Default")
      (node (ref "U1") (pin "99") (pinfunction "I/O_99") (pintype "bidirectional"))
    )
    (net (code "110") (name "unconnected-(U1E-I{slash}O_(DLL),_L31P-Pad81)") (class "Default")
      (node (ref "U1") (pin "81") (pinfunction "I/O_(DLL),_L31P_81") (pintype "bidirectional"))
    )
    (net (code "111") (name "unconnected-(U1F-I{slash}O,_L32N-Pad71)") (class "Default")
      (node (ref "U1") (pin "71") (pinfunction "I/O,_L32N_71") (pintype "bidirectional"))
    )
    (net (code "112") (name "unconnected-(U1F-I{slash}O,_L33N_Y-Pad68)") (class "Default")
      (node (ref "U1") (pin "68") (pinfunction "I/O,_L33N_Y_68") (pintype "bidirectional"))
    )
    (net (code "113") (name "unconnected-(U1F-I{slash}O,_L33P_Y-Pad69)") (class "Default")
      (node (ref "U1") (pin "69") (pinfunction "I/O,_L33P_Y_69") (pintype "bidirectional"))
    )
    (net (code "114") (name "unconnected-(U1F-I{slash}O,_L34P_Y-Pad64)") (class "Default")
      (node (ref "U1") (pin "64") (pinfunction "I/O,_L34P_Y_64") (pintype "bidirectional"))
    )
    (net (code "115") (name "unconnected-(U1F-I{slash}O,_L35N-Pad61)") (class "Default")
      (node (ref "U1") (pin "61") (pinfunction "I/O,_L35N_61") (pintype "bidirectional"))
    )
    (net (code "116") (name "unconnected-(U1F-I{slash}O,_L35P-Pad62)") (class "Default")
      (node (ref "U1") (pin "62") (pinfunction "I/O,_L35P_62") (pintype "bidirectional"))
    )
    (net (code "117") (name "unconnected-(U1F-I{slash}O,_L36P_YY-Pad60)") (class "Default")
      (node (ref "U1") (pin "60") (pinfunction "I/O,_L36P_YY_60") (pintype "bidirectional"))
    )
    (net (code "118") (name "unconnected-(U1F-I{slash}O,_L37N_YY-Pad55)") (class "Default")
      (node (ref "U1") (pin "55") (pinfunction "I/O,_L37N_YY_55") (pintype "bidirectional"))
    )
    (net (code "119") (name "unconnected-(U1F-I{slash}O,_L37P_YY-Pad56)") (class "Default")
      (node (ref "U1") (pin "56") (pinfunction "I/O,_L37P_YY_56") (pintype "bidirectional"))
    )
    (net (code "120") (name "unconnected-(U1F-I{slash}O,_VREF_5,_L32P-Pad73)") (class "Default")
      (node (ref "U1") (pin "73") (pinfunction "I/O,_VREF_5,_L32P_73") (pintype "bidirectional"))
    )
    (net (code "121") (name "unconnected-(U1F-I{slash}O,_VREF_5,_L34N_Y-Pad63)") (class "Default")
      (node (ref "U1") (pin "63") (pinfunction "I/O,_VREF_5,_L34N_Y_63") (pintype "bidirectional"))
    )
    (net (code "122") (name "unconnected-(U1F-I{slash}O,_VREF_5,_L36N_YY-Pad59)") (class "Default")
      (node (ref "U1") (pin "59") (pinfunction "I/O,_VREF_5,_L36N_YY_59") (pintype "bidirectional"))
    )
    (net (code "123") (name "unconnected-(U1F-I{slash}O,_VREF_5-Pad57)") (class "Default")
      (node (ref "U1") (pin "57") (pinfunction "I/O,_VREF_5_57") (pintype "bidirectional"))
    )
    (net (code "124") (name "unconnected-(U1F-I{slash}O-Pad58)") (class "Default")
      (node (ref "U1") (pin "58") (pinfunction "I/O_58") (pintype "bidirectional"))
    )
    (net (code "125") (name "unconnected-(U1F-I{slash}O-Pad70)") (class "Default")
      (node (ref "U1") (pin "70") (pinfunction "I/O_70") (pintype "bidirectional"))
    )
    (net (code "126") (name "unconnected-(U1F-I{slash}O-Pad74)") (class "Default")
      (node (ref "U1") (pin "74") (pinfunction "I/O_74") (pintype "bidirectional"))
    )
    (net (code "127") (name "unconnected-(U1F-I{slash}O_(DLL),_L31N-Pad75)") (class "Default")
      (node (ref "U1") (pin "75") (pinfunction "I/O_(DLL),_L31N_75") (pintype "bidirectional"))
    )
    (net (code "128") (name "unconnected-(U1G-I{slash}O,_L38N_YY-Pad49)") (class "Default")
      (node (ref "U1") (pin "49") (pinfunction "I/O,_L38N_YY_49") (pintype "bidirectional"))
    )
    (net (code "129") (name "unconnected-(U1G-I{slash}O,_L38P_YY-Pad48)") (class "Default")
      (node (ref "U1") (pin "48") (pinfunction "I/O,_L38P_YY_48") (pintype "bidirectional"))
    )
    (net (code "130") (name "unconnected-(U1G-I{slash}O,_L39N-Pad46)") (class "Default")
      (node (ref "U1") (pin "46") (pinfunction "I/O,_L39N_46") (pintype "bidirectional"))
    )
    (net (code "131") (name "unconnected-(U1G-I{slash}O,_L40P-Pad40)") (class "Default")
      (node (ref "U1") (pin "40") (pinfunction "I/O,_L40P_40") (pintype "bidirectional"))
    )
    (net (code "132") (name "unconnected-(U1G-I{slash}O,_L41N_YY-Pad36)") (class "Default")
      (node (ref "U1") (pin "36") (pinfunction "I/O,_L41N_YY_36") (pintype "bidirectional"))
    )
    (net (code "133") (name "unconnected-(U1G-I{slash}O,_L41P_YY-Pad35)") (class "Default")
      (node (ref "U1") (pin "35") (pinfunction "I/O,_L41P_YY_35") (pintype "bidirectional"))
    )
    (net (code "134") (name "unconnected-(U1G-I{slash}O,_L42N_YY-Pad34)") (class "Default")
      (node (ref "U1") (pin "34") (pinfunction "I/O,_L42N_YY_34") (pintype "bidirectional"))
    )
    (net (code "135") (name "unconnected-(U1G-I{slash}O,_L42P_YY-Pad33)") (class "Default")
      (node (ref "U1") (pin "33") (pinfunction "I/O,_L42P_YY_33") (pintype "bidirectional"))
    )
    (net (code "136") (name "unconnected-(U1G-I{slash}O,_L43P-Pad30)") (class "Default")
      (node (ref "U1") (pin "30") (pinfunction "I/O,_L43P_30") (pintype "bidirectional"))
    )
    (net (code "137") (name "unconnected-(U1G-I{slash}O,_VREF_6,_L39P-Pad45)") (class "Default")
      (node (ref "U1") (pin "45") (pinfunction "I/O,_VREF_6,_L39P_45") (pintype "bidirectional"))
    )
    (net (code "138") (name "unconnected-(U1G-I{slash}O,_VREF_6,_L40N-Pad41)") (class "Default")
      (node (ref "U1") (pin "41") (pinfunction "I/O,_VREF_6,_L40N_41") (pintype "bidirectional"))
    )
    (net (code "139") (name "unconnected-(U1G-I{slash}O,_VREF_6,_L43N-Pad31)") (class "Default")
      (node (ref "U1") (pin "31") (pinfunction "I/O,_VREF_6,_L43N_31") (pintype "bidirectional"))
    )
    (net (code "140") (name "unconnected-(U1G-I{slash}O,_VREF_6-Pad47)") (class "Default")
      (node (ref "U1") (pin "47") (pinfunction "I/O,_VREF_6_47") (pintype "bidirectional"))
    )
    (net (code "141") (name "unconnected-(U1G-I{slash}O-Pad29)") (class "Default")
      (node (ref "U1") (pin "29") (pinfunction "I/O_29") (pintype "bidirectional"))
    )
    (net (code "142") (name "unconnected-(U1G-I{slash}O-Pad42)") (class "Default")
      (node (ref "U1") (pin "42") (pinfunction "I/O_42") (pintype "bidirectional"))
    )
    (net (code "143") (name "unconnected-(U1G-I{slash}O-Pad43)") (class "Default")
      (node (ref "U1") (pin "43") (pinfunction "I/O_43") (pintype "bidirectional"))
    )
    (net (code "144") (name "unconnected-(U1G-I{slash}O-Pad44)") (class "Default")
      (node (ref "U1") (pin "44") (pinfunction "I/O_44") (pintype "bidirectional"))
    )
    (net (code "145") (name "unconnected-(U1G-I{slash}O_(TRDY)-Pad27)") (class "Default")
      (node (ref "U1") (pin "27") (pinfunction "I/O_(TRDY)_27") (pintype "bidirectional"))
    )
    (net (code "146") (name "unconnected-(U1H-I{slash}O,_L44P_YY-Pad23)") (class "Default")
      (node (ref "U1") (pin "23") (pinfunction "I/O,_L44P_YY_23") (pintype "bidirectional"))
    )
    (net (code "147") (name "unconnected-(U1H-I{slash}O,_L45N-Pad21)") (class "Default")
      (node (ref "U1") (pin "21") (pinfunction "I/O,_L45N_21") (pintype "bidirectional"))
    )
    (net (code "148") (name "unconnected-(U1H-I{slash}O,_L46N_YY-Pad18)") (class "Default")
      (node (ref "U1") (pin "18") (pinfunction "I/O,_L46N_YY_18") (pintype "bidirectional"))
    )
    (net (code "149") (name "unconnected-(U1H-I{slash}O,_L46P_YY-Pad17)") (class "Default")
      (node (ref "U1") (pin "17") (pinfunction "I/O,_L46P_YY_17") (pintype "bidirectional"))
    )
    (net (code "150") (name "unconnected-(U1H-I{slash}O,_L47N_YY-Pad16)") (class "Default")
      (node (ref "U1") (pin "16") (pinfunction "I/O,_L47N_YY_16") (pintype "bidirectional"))
    )
    (net (code "151") (name "unconnected-(U1H-I{slash}O,_L47P_YY-Pad15)") (class "Default")
      (node (ref "U1") (pin "15") (pinfunction "I/O,_L47P_YY_15") (pintype "bidirectional"))
    )
    (net (code "152") (name "unconnected-(U1H-I{slash}O,_L48N-Pad11)") (class "Default")
      (node (ref "U1") (pin "11") (pinfunction "I/O,_L48N_11") (pintype "bidirectional"))
    )
    (net (code "153") (name "unconnected-(U1H-I{slash}O,_L49N_Y-Pad7)") (class "Default")
      (node (ref "U1") (pin "7") (pinfunction "I/O,_L49N_Y_7") (pintype "bidirectional"))
    )
    (net (code "154") (name "unconnected-(U1H-I{slash}O,_VREF_7,_L45P-Pad20)") (class "Default")
      (node (ref "U1") (pin "20") (pinfunction "I/O,_VREF_7,_L45P_20") (pintype "bidirectional"))
    )
    (net (code "155") (name "unconnected-(U1H-I{slash}O,_VREF_7,_L48P-Pad10)") (class "Default")
      (node (ref "U1") (pin "10") (pinfunction "I/O,_VREF_7,_L48P_10") (pintype "bidirectional"))
    )
    (net (code "156") (name "unconnected-(U1H-I{slash}O,_VREF_7,_L49P_Y-Pad6)") (class "Default")
      (node (ref "U1") (pin "6") (pinfunction "I/O,_VREF_7,_L49P_Y_6") (pintype "bidirectional"))
    )
    (net (code "157") (name "unconnected-(U1H-I{slash}O,_VREF_7-Pad4)") (class "Default")
      (node (ref "U1") (pin "4") (pinfunction "I/O,_VREF_7_4") (pintype "bidirectional"))
    )
    (net (code "158") (name "unconnected-(U1H-I{slash}O-Pad3)") (class "Default")
      (node (ref "U1") (pin "3") (pinfunction "I/O_3") (pintype "bidirectional"))
    )
    (net (code "159") (name "unconnected-(U1H-I{slash}O-Pad5)") (class "Default")
      (node (ref "U1") (pin "5") (pinfunction "I/O_5") (pintype "bidirectional"))
    )
    (net (code "160") (name "unconnected-(U1H-I{slash}O-Pad8)") (class "Default")
      (node (ref "U1") (pin "8") (pinfunction "I/O_8") (pintype "bidirectional"))
    )
    (net (code "161") (name "unconnected-(U1H-I{slash}O-Pad9)") (class "Default")
      (node (ref "U1") (pin "9") (pinfunction "I/O_9") (pintype "bidirectional"))
    )
    (net (code "162") (name "unconnected-(U1H-I{slash}O-Pad22)") (class "Default")
      (node (ref "U1") (pin "22") (pinfunction "I/O_22") (pintype "bidirectional"))
    )
    (net (code "163") (name "unconnected-(U1H-I{slash}O_(IRDY),_L44N_YY-Pad24)") (class "Default")
      (node (ref "U1") (pin "24") (pinfunction "I/O_(IRDY),_L44N_YY_24") (pintype "bidirectional"))
    )
    (net (code "164") (name "unconnected-(U1I-GCK0,_I-Pad80)") (class "Default")
      (node (ref "U1") (pin "80") (pinfunction "GCK0,_I_80") (pintype "input"))
    )
    (net (code "165") (name "unconnected-(U1I-GCK1,_I-Pad77)") (class "Default")
      (node (ref "U1") (pin "77") (pinfunction "GCK1,_I_77") (pintype "input"))
    )
    (net (code "166") (name "unconnected-(U1I-GCK2,_I-Pad182)") (class "Default")
      (node (ref "U1") (pin "182") (pinfunction "GCK2,_I_182") (pintype "input"))
    )
    (net (code "167") (name "unconnected-(U1I-GCK3,_I-Pad185)") (class "Default")
      (node (ref "U1") (pin "185") (pinfunction "GCK3,_I_185") (pintype "input"))
    )
    (net (code "168") (name "unconnected-(U1J-CCLK-Pad155)") (class "Default")
      (node (ref "U1") (pin "155") (pinfunction "CCLK_155") (pintype "bidirectional"))
    )
    (net (code "169") (name "unconnected-(U1J-DIN-Pad153)") (class "Default")
      (node (ref "U1") (pin "153") (pinfunction "DIN_153") (pintype "bidirectional"))
    )
    (net (code "170") (name "unconnected-(U1J-DONE-Pad104)") (class "Default")
      (node (ref "U1") (pin "104") (pinfunction "DONE_104") (pintype "bidirectional"))
    )
    (net (code "171") (name "unconnected-(U1J-M0-Pad52)") (class "Default")
      (node (ref "U1") (pin "52") (pinfunction "M0_52") (pintype "input"))
    )
    (net (code "172") (name "unconnected-(U1J-M1-Pad50)") (class "Default")
      (node (ref "U1") (pin "50") (pinfunction "M1_50") (pintype "input"))
    )
    (net (code "173") (name "unconnected-(U1J-M2-Pad54)") (class "Default")
      (node (ref "U1") (pin "54") (pinfunction "M2_54") (pintype "input"))
    )
    (net (code "174") (name "unconnected-(U1J-PROGRAM-Pad106)") (class "Default")
      (node (ref "U1") (pin "106") (pinfunction "PROGRAM_106") (pintype "input"))
    )
    (net (code "175") (name "unconnected-(U1J-TCK-Pad207)") (class "Default")
      (node (ref "U1") (pin "207") (pinfunction "TCK_207") (pintype "input"))
    )
    (net (code "176") (name "unconnected-(U1J-TDI-Pad159)") (class "Default")
      (node (ref "U1") (pin "159") (pinfunction "TDI_159") (pintype "input"))
    )
    (net (code "177") (name "unconnected-(U1J-TDO-Pad157)") (class "Default")
      (node (ref "U1") (pin "157") (pinfunction "TDO_157") (pintype "output"))
    )
    (net (code "178") (name "unconnected-(U1J-TMS-Pad2)") (class "Default")
      (node (ref "U1") (pin "2") (pinfunction "TMS_2") (pintype "input"))
    )
    (net (code "179") (name "unconnected-(U1J-~{INIT}-Pad107)") (class "Default")
      (node (ref "U1") (pin "107") (pinfunction "~{INIT}_107") (pintype "bidirectional"))
    )
    (net (code "180") (name "unconnected-(U2-4Y4-Pad23)") (class "Default")
      (node (ref "U2") (pin "23") (pinfunction "4Y4_23") (pintype "tri_state"))
    )
    (net (code "181") (name "unconnected-(U3-1Y1-Pad2)") (class "Default")
      (node (ref "U3") (pin "2") (pinfunction "1Y1_2") (pintype "tri_state"))
    )
    (net (code "182") (name "unconnected-(U3-1Y2-Pad3)") (class "Default")
      (node (ref "U3") (pin "3") (pinfunction "1Y2_3") (pintype "tri_state"))
    )
    (net (code "183") (name "unconnected-(U3-1Y3-Pad5)") (class "Default")
      (node (ref "U3") (pin "5") (pinfunction "1Y3_5") (pintype "tri_state"))
    )
    (net (code "184") (name "unconnected-(U3-1Y4-Pad6)") (class "Default")
      (node (ref "U3") (pin "6") (pinfunction "1Y4_6") (pintype "tri_state"))
    )
    (net (code "185") (name "unconnected-(U3-2Y1-Pad8)") (class "Default")
      (node (ref "U3") (pin "8") (pinfunction "2Y1_8") (pintype "tri_state"))
    )
    (net (code "186") (name "unconnected-(U3-2Y2-Pad9)") (class "Default")
      (node (ref "U3") (pin "9") (pinfunction "2Y2_9") (pintype "tri_state"))
    )
    (net (code "187") (name "unconnected-(U3-2Y3-Pad11)") (class "Default")
      (node (ref "U3") (pin "11") (pinfunction "2Y3_11") (pintype "tri_state"))
    )
    (net (code "188") (name "unconnected-(U3-2Y4-Pad12)") (class "Default")
      (node (ref "U3") (pin "12") (pinfunction "2Y4_12") (pintype "tri_state"))
    )
    (net (code "189") (name "unconnected-(U3-3Y1-Pad13)") (class "Default")
      (node (ref "U3") (pin "13") (pinfunction "3Y1_13") (pintype "tri_state"))
    )
    (net (code "190") (name "unconnected-(U3-3Y2-Pad14)") (class "Default")
      (node (ref "U3") (pin "14") (pinfunction "3Y2_14") (pintype "tri_state"))
    )
    (net (code "191") (name "unconnected-(U3-3Y3-Pad16)") (class "Default")
      (node (ref "U3") (pin "16") (pinfunction "3Y3_16") (pintype "tri_state"))
    )
    (net (code "192") (name "unconnected-(U3-3Y4-Pad17)") (class "Default")
      (node (ref "U3") (pin "17") (pinfunction "3Y4_17") (pintype "tri_state"))
    )
    (net (code "193") (name "unconnected-(U3-4Y1-Pad19)") (class "Default")
      (node (ref "U3") (pin "19") (pinfunction "4Y1_19") (pintype "tri_state"))
    )
    (net (code "194") (name "unconnected-(U3-4Y2-Pad20)") (class "Default")
      (node (ref "U3") (pin "20") (pinfunction "4Y2_20") (pintype "tri_state"))
    )
    (net (code "195") (name "unconnected-(U3-4Y3-Pad22)") (class "Default")
      (node (ref "U3") (pin "22") (pinfunction "4Y3_22") (pintype "tri_state"))
    )
    (net (code "196") (name "unconnected-(U3-4Y4-Pad23)") (class "Default")
      (node (ref "U3") (pin "23") (pinfunction "4Y4_23") (pintype "tri_state"))
    )
    (net (code "197") (name "unconnected-(U4-GND-Pad10)") (class "Default")
      (node (ref "U4") (pin "10") (pinfunction "GND_10") (pintype "power_in"))
    )
    (net (code "198") (name "unconnected-(U4-VCC-Pad20)") (class "Default")
      (node (ref "U4") (pin "20") (pinfunction "VCC_20") (pintype "power_in"))
    )
    (net (code "199") (name "unconnected-(U4-~{OE}1-Pad1)") (class "Default")
      (node (ref "U4") (pin "1") (pinfunction "~{OE}1_1") (pintype "input"))
    )
    (net (code "200") (name "unconnected-(U4-~{OE}2-Pad19)") (class "Default")
      (node (ref "U4") (pin "19") (pinfunction "~{OE}2_19") (pintype "input"))
    )
    (net (code "201") (name "unconnected-(U4-~{Y}1-Pad18)") (class "Default")
      (node (ref "U4") (pin "18") (pinfunction "~{Y}1_18") (pintype "tri_state"))
    )
    (net (code "202") (name "unconnected-(U4-~{Y}2-Pad16)") (class "Default")
      (node (ref "U4") (pin "16") (pinfunction "~{Y}2_16") (pintype "tri_state"))
    )
    (net (code "203") (name "unconnected-(U4-~{Y}3-Pad14)") (class "Default")
      (node (ref "U4") (pin "14") (pinfunction "~{Y}3_14") (pintype "tri_state"))
    )
    (net (code "204") (name "unconnected-(U4-~{Y}4-Pad12)") (class "Default")
      (node (ref "U4") (pin "12") (pinfunction "~{Y}4_12") (pintype "tri_state"))
    )
    (net (code "205") (name "unconnected-(U4-~{Y}5-Pad9)") (class "Default")
      (node (ref "U4") (pin "9") (pinfunction "~{Y}5_9") (pintype "tri_state"))
    )
    (net (code "206") (name "unconnected-(U4-~{Y}6-Pad7)") (class "Default")
      (node (ref "U4") (pin "7") (pinfunction "~{Y}6_7") (pintype "tri_state"))
    )
    (net (code "207") (name "unconnected-(U4-~{Y}7-Pad5)") (class "Default")
      (node (ref "U4") (pin "5") (pinfunction "~{Y}7_5") (pintype "tri_state"))
    )
    (net (code "208") (name "unconnected-(U4-~{Y}8-Pad3)") (class "Default")
      (node (ref "U4") (pin "3") (pinfunction "~{Y}8_3") (pintype "tri_state"))
    )
    (net (code "209") (name "unconnected-(U5-GND-Pad10)") (class "Default")
      (node (ref "U5") (pin "10") (pinfunction "GND_10") (pintype "power_in"))
    )
    (net (code "210") (name "unconnected-(U5-VCC-Pad20)") (class "Default")
      (node (ref "U5") (pin "20") (pinfunction "VCC_20") (pintype "power_in"))
    )
    (net (code "211") (name "unconnected-(U5-~{OE}1-Pad1)") (class "Default")
      (node (ref "U5") (pin "1") (pinfunction "~{OE}1_1") (pintype "input"))
    )
    (net (code "212") (name "unconnected-(U5-~{OE}2-Pad19)") (class "Default")
      (node (ref "U5") (pin "19") (pinfunction "~{OE}2_19") (pintype "input"))
    )
    (net (code "213") (name "unconnected-(U5-~{Y}1-Pad18)") (class "Default")
      (node (ref "U5") (pin "18") (pinfunction "~{Y}1_18") (pintype "tri_state"))
    )
    (net (code "214") (name "unconnected-(U5-~{Y}2-Pad16)") (class "Default")
      (node (ref "U5") (pin "16") (pinfunction "~{Y}2_16") (pintype "tri_state"))
    )
    (net (code "215") (name "unconnected-(U5-~{Y}3-Pad14)") (class "Default")
      (node (ref "U5") (pin "14") (pinfunction "~{Y}3_14") (pintype "tri_state"))
    )
    (net (code "216") (name "unconnected-(U5-~{Y}4-Pad12)") (class "Default")
      (node (ref "U5") (pin "12") (pinfunction "~{Y}4_12") (pintype "tri_state"))
    )
    (net (code "217") (name "unconnected-(U5-~{Y}5-Pad9)") (class "Default")
      (node (ref "U5") (pin "9") (pinfunction "~{Y}5_9") (pintype "tri_state"))
    )
    (net (code "218") (name "unconnected-(U5-~{Y}6-Pad7)") (class "Default")
      (node (ref "U5") (pin "7") (pinfunction "~{Y}6_7") (pintype "tri_state"))
    )
    (net (code "219") (name "unconnected-(U5-~{Y}7-Pad5)") (class "Default")
      (node (ref "U5") (pin "5") (pinfunction "~{Y}7_5") (pintype "tri_state"))
    )
    (net (code "220") (name "unconnected-(U5-~{Y}8-Pad3)") (class "Default")
      (node (ref "U5") (pin "3") (pinfunction "~{Y}8_3") (pintype "tri_state"))
    )
    (net (code "221") (name "unconnected-(U6-GND-Pad10)") (class "Default")
      (node (ref "U6") (pin "10") (pinfunction "GND_10") (pintype "power_in"))
    )
    (net (code "222") (name "unconnected-(U6-VCC-Pad20)") (class "Default")
      (node (ref "U6") (pin "20") (pinfunction "VCC_20") (pintype "power_in"))
    )
    (net (code "223") (name "unconnected-(U6-~{OE}1-Pad1)") (class "Default")
      (node (ref "U6") (pin "1") (pinfunction "~{OE}1_1") (pintype "input"))
    )
    (net (code "224") (name "unconnected-(U6-~{OE}2-Pad19)") (class "Default")
      (node (ref "U6") (pin "19") (pinfunction "~{OE}2_19") (pintype "input"))
    )
    (net (code "225") (name "unconnected-(U6-~{Y}1-Pad18)") (class "Default")
      (node (ref "U6") (pin "18") (pinfunction "~{Y}1_18") (pintype "tri_state"))
    )
    (net (code "226") (name "unconnected-(U6-~{Y}2-Pad16)") (class "Default")
      (node (ref "U6") (pin "16") (pinfunction "~{Y}2_16") (pintype "tri_state"))
    )
    (net (code "227") (name "unconnected-(U6-~{Y}3-Pad14)") (class "Default")
      (node (ref "U6") (pin "14") (pinfunction "~{Y}3_14") (pintype "tri_state"))
    )
    (net (code "228") (name "unconnected-(U6-~{Y}4-Pad12)") (class "Default")
      (node (ref "U6") (pin "12") (pinfunction "~{Y}4_12") (pintype "tri_state"))
    )
    (net (code "229") (name "unconnected-(U6-~{Y}5-Pad9)") (class "Default")
      (node (ref "U6") (pin "9") (pinfunction "~{Y}5_9") (pintype "tri_state"))
    )
    (net (code "230") (name "unconnected-(U6-~{Y}6-Pad7)") (class "Default")
      (node (ref "U6") (pin "7") (pinfunction "~{Y}6_7") (pintype "tri_state"))
    )
    (net (code "231") (name "unconnected-(U6-~{Y}7-Pad5)") (class "Default")
      (node (ref "U6") (pin "5") (pinfunction "~{Y}7_5") (pintype "tri_state"))
    )
    (net (code "232") (name "unconnected-(U6-~{Y}8-Pad3)") (class "Default")
      (node (ref "U6") (pin "3") (pinfunction "~{Y}8_3") (pintype "tri_state"))
    )
  )
)
